# ADC.net
KiCad netlist of a schematic drawn in Altium Designer
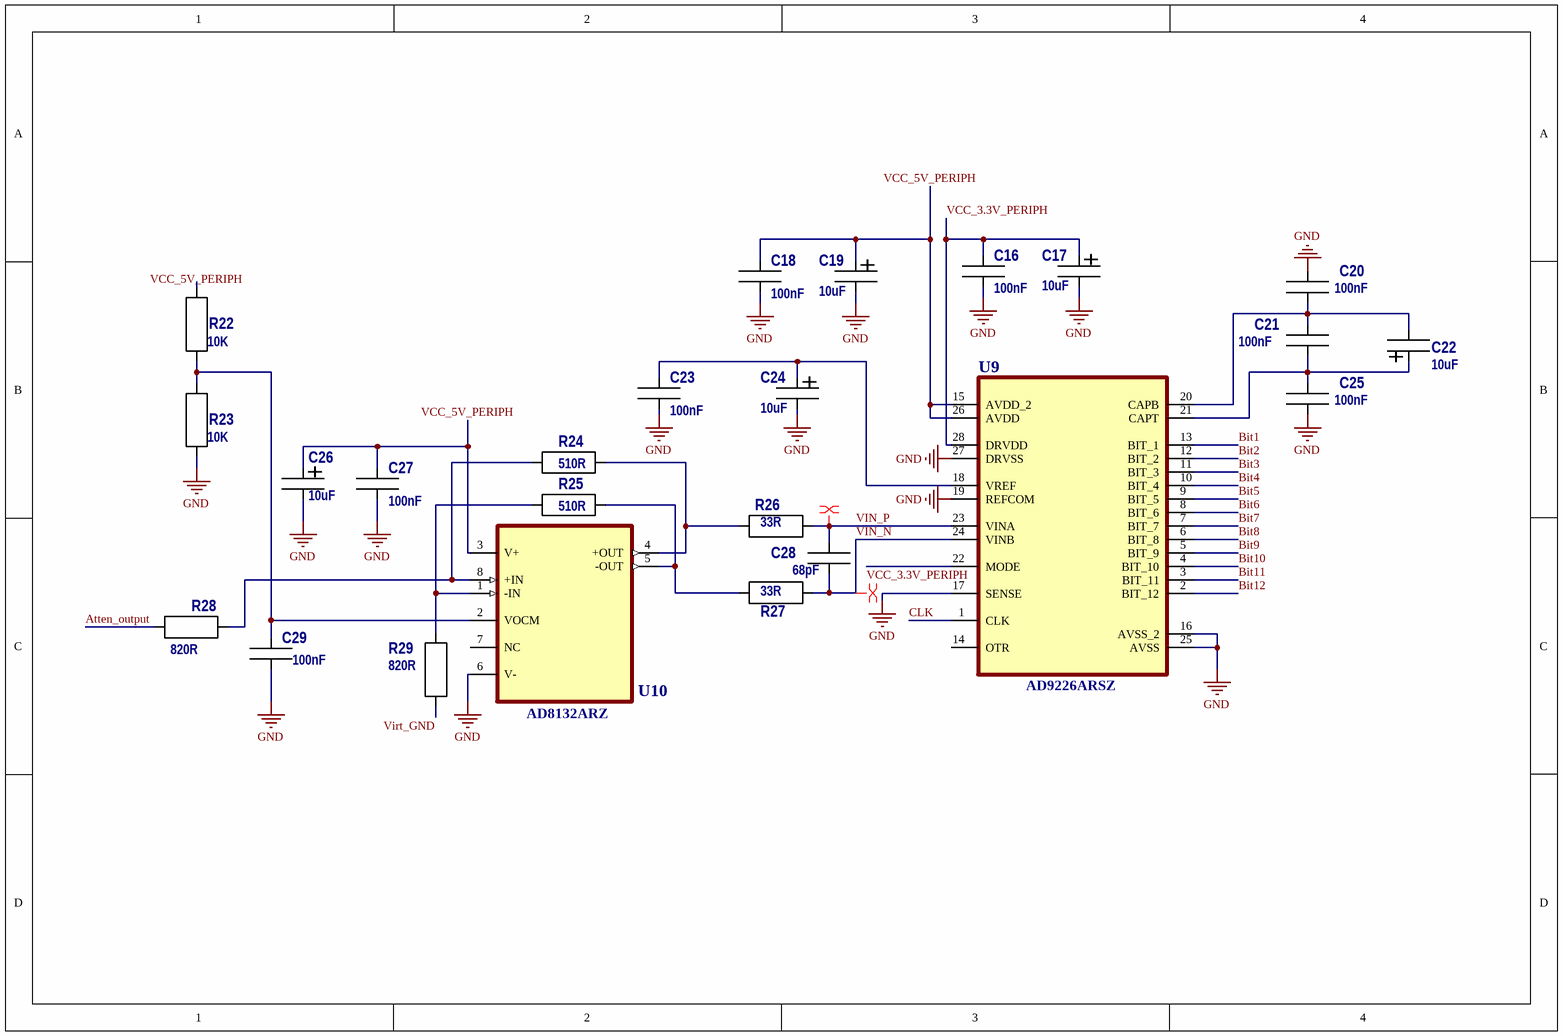
[diagram p0: ADC.SchDoc]

(export (version "E")
  (design (tool "Eeschema 10.0.6"))
  (components
    (comp (ref "C16")
      (value "100nF")
      (footprint "CAP 0603 3D")
      (description "0603 100nF X7R")
      (libsource (lib "RLC V7.1_BVI") (part "C"))
    )
    (comp (ref "C17")
      (value "10uF")
      (footprint "Tant B")
      (description "SMD type B 10 uF min 16V")
      (libsource (lib "RLC V7.1_BVI") (part "C T"))
    )
    (comp (ref "C18")
      (value "100nF")
      (footprint "CAP 0603 3D")
      (description "0603 100nF X7R")
      (libsource (lib "RLC V7.1_BVI") (part "C"))
    )
    (comp (ref "C19")
      (value "10uF")
      (footprint "Tant B")
      (description "SMD type B 10 uF min 16V")
      (libsource (lib "RLC V7.1_BVI") (part "C T"))
    )
    (comp (ref "C20")
      (value "100nF")
      (footprint "CAP 0603 3D")
      (description "0603 100nF X7R")
      (libsource (lib "RLC V7.1_BVI") (part "C"))
    )
    (comp (ref "C21")
      (value "100nF")
      (footprint "CAP 0603 3D")
      (description "0603 100nF X7R")
      (libsource (lib "RLC V7.1_BVI") (part "C"))
    )
    (comp (ref "C22")
      (value "10uF")
      (footprint "Tant B")
      (description "SMD type B 10 uF min 16V")
      (libsource (lib "RLC V7.1_BVI") (part "C T"))
    )
    (comp (ref "C23")
      (value "100nF")
      (footprint "CAP 0603 3D")
      (description "0603 100nF X7R")
      (libsource (lib "RLC V7.1_BVI") (part "C"))
    )
    (comp (ref "C24")
      (value "10uF")
      (footprint "Tant B")
      (description "SMD type B 10 uF min 16V")
      (libsource (lib "RLC V7.1_BVI") (part "C T"))
    )
    (comp (ref "C25")
      (value "100nF")
      (footprint "CAP 0603 3D")
      (description "0603 100nF X7R")
      (libsource (lib "RLC V7.1_BVI") (part "C"))
    )
    (comp (ref "C26")
      (value "10uF")
      (footprint "Tant B")
      (description "SMD type B 10 uF min 16V")
      (libsource (lib "RLC V7.1_BVI") (part "C T"))
    )
    (comp (ref "C27")
      (value "100nF")
      (footprint "cap 1206 3D")
      (description "0603 100nF X7R")
      (libsource (lib "RLC V7.1_BVI") (part "C"))
    )
    (comp (ref "C28")
      (value "68pF")
      (footprint "CAP 0603 3D")
      (description "0805 68pF NP0 (C0G)")
      (libsource (lib "RLC V7.1_BVI") (part "C"))
    )
    (comp (ref "C29")
      (value "100nF")
      (footprint "CAP 0603 3D")
      (description "0603 100nF X7R")
      (libsource (lib "RLC V7.1_BVI") (part "C"))
    )
    (comp (ref "R22")
      (value "10K")
      (footprint "Res_0603 3D")
      (description "10K 0805")
      (libsource (lib "RLC V7.1_BVI") (part "R"))
    )
    (comp (ref "R23")
      (value "10K")
      (footprint "Res_0603 3D")
      (description "10K 0805")
      (libsource (lib "RLC V7.1_BVI") (part "R"))
    )
    (comp (ref "R24")
      (value "510R")
      (footprint "Res_0603 3D")
      (description "0805 0.1%")
      (libsource (lib "RLC V7.1_BVI") (part "R"))
    )
    (comp (ref "R25")
      (value "510R")
      (footprint "Res_0603 3D")
      (description "0805 0.1%")
      (libsource (lib "RLC V7.1_BVI") (part "R"))
    )
    (comp (ref "R26")
      (value "33R")
      (footprint "Res_0603 3D")
      (description "0805 0.1%")
      (libsource (lib "RLC V7.1_BVI") (part "R"))
    )
    (comp (ref "R27")
      (value "33R")
      (footprint "Res_0603 3D")
      (description "0805 0.1%")
      (libsource (lib "RLC V7.1_BVI") (part "R"))
    )
    (comp (ref "R28")
      (value "820R")
      (footprint "Res_0603 3D")
      (description "0805 0.1%")
      (libsource (lib "RLC V7.1_BVI") (part "R"))
    )
    (comp (ref "R29")
      (value "820R")
      (footprint "Res_0603 3D")
      (description "0805 0.1%")
      (libsource (lib "RLC V7.1_BVI") (part "R"))
    )
    (comp (ref "U9")
      (value "AD9226ARSZ")
      (footprint "SOP65P780X200-28N")
      (description "12-Bit, 65 MSPS Analog-to-Digital Converter")
      (fields (field (name "MF") "Analog Devices"))
      (libsource (lib "AD9226ARSZ") (part "AD9226ARSZ"))
    )
    (comp (ref "U10")
      (value "AD8132ARZ")
      (footprint "SOIC127P600X175-8N")
      (description "Low Cost, High Speed Differential Amplifier")
      (fields (field (name "MF") "Analog Devices"))
      (libsource (lib "AD8132ARZ") (part "AD8132ARZ"))
    )
  )
  (nets
    (net (code "1") (name "/Atten_output") (class "Default") (node (ref "R28") (pin "2") (pintype "passive")))
    (net (code "2") (name "/Bit1") (class "Default")
      (node (ref "U9") (pin "13") (pinfunction "BIT_1_13") (pintype "passive"))
    )
    (net (code "3") (name "/Bit2") (class "Default")
      (node (ref "U9") (pin "12") (pinfunction "BIT_2_12") (pintype "passive"))
    )
    (net (code "4") (name "/Bit3") (class "Default")
      (node (ref "U9") (pin "11") (pinfunction "BIT_3_11") (pintype "passive"))
    )
    (net (code "5") (name "/Bit4") (class "Default")
      (node (ref "U9") (pin "10") (pinfunction "BIT_4_10") (pintype "passive"))
    )
    (net (code "6") (name "/Bit5") (class "Default")
      (node (ref "U9") (pin "9") (pinfunction "BIT_5_9") (pintype "passive"))
    )
    (net (code "7") (name "/Bit6") (class "Default")
      (node (ref "U9") (pin "8") (pinfunction "BIT_6_8") (pintype "passive"))
    )
    (net (code "8") (name "/Bit7") (class "Default")
      (node (ref "U9") (pin "7") (pinfunction "BIT_7_7") (pintype "passive"))
    )
    (net (code "9") (name "/Bit8") (class "Default")
      (node (ref "U9") (pin "6") (pinfunction "BIT_8_6") (pintype "passive"))
    )
    (net (code "10") (name "/Bit9") (class "Default")
      (node (ref "U9") (pin "5") (pinfunction "BIT_9_5") (pintype "passive"))
    )
    (net (code "11") (name "/Bit10") (class "Default")
      (node (ref "U9") (pin "4") (pinfunction "BIT_10_4") (pintype "passive"))
    )
    (net (code "12") (name "/Bit11") (class "Default")
      (node (ref "U9") (pin "3") (pinfunction "BIT_11_3") (pintype "passive"))
    )
    (net (code "13") (name "/Bit12") (class "Default")
      (node (ref "U9") (pin "2") (pinfunction "BIT_12_2") (pintype "passive"))
    )
    (net (code "14") (name "/CLK") (class "Default")
      (node (ref "U9") (pin "1") (pinfunction "CLK_1") (pintype "passive"))
    )
    (net (code "15") (name "/VCC_3.3V_PERIPH") (class "Default")
      (node (ref "C16") (pin "1") (pintype "passive"))
      (node (ref "C17") (pin "1") (pinfunction "+_1") (pintype "passive"))
      (node (ref "U9") (pin "22") (pinfunction "MODE_22") (pintype "passive"))
      (node (ref "U9") (pin "28") (pinfunction "DRVDD_28") (pintype "passive"))
    )
    (net (code "16") (name "/VCC_5V_PERIPH") (class "Default")
      (node (ref "C18") (pin "1") (pintype "passive"))
      (node (ref "C19") (pin "1") (pinfunction "+_1") (pintype "passive"))
      (node (ref "C26") (pin "1") (pinfunction "+_1") (pintype "passive"))
      (node (ref "C27") (pin "1") (pintype "passive"))
      (node (ref "R22") (pin "2") (pintype "passive"))
      (node (ref "U10") (pin "3") (pinfunction "V+_3") (pintype "power_in"))
      (node (ref "U9") (pin "15") (pinfunction "AVDD_2_15") (pintype "passive"))
      (node (ref "U9") (pin "26") (pinfunction "AVDD_26") (pintype "passive"))
    )
    (net (code "17") (name "/VIN_N") (class "Default")
      (node (ref "C28") (pin "2") (pintype "passive"))
      (node (ref "R27") (pin "1") (pintype "passive"))
      (node (ref "U9") (pin "24") (pinfunction "VINB_24") (pintype "passive"))
    )
    (net (code "18") (name "/VIN_P") (class "Default")
      (node (ref "C28") (pin "1") (pintype "passive"))
      (node (ref "R26") (pin "1") (pintype "passive"))
      (node (ref "U9") (pin "23") (pinfunction "VINA_23") (pintype "passive"))
    )
    (net (code "19") (name "/Virt_GND") (class "Default") (node (ref "R29") (pin "2") (pintype "passive")))
    (net (code "20") (name "GND") (class "Default")
      (node (ref "C16") (pin "2") (pintype "passive"))
      (node (ref "C17") (pin "2") (pinfunction "-_2") (pintype "passive"))
      (node (ref "C18") (pin "2") (pintype "passive"))
      (node (ref "C19") (pin "2") (pinfunction "-_2") (pintype "passive"))
      (node (ref "C20") (pin "1") (pintype "passive"))
      (node (ref "C23") (pin "2") (pintype "passive"))
      (node (ref "C24") (pin "2") (pinfunction "-_2") (pintype "passive"))
      (node (ref "C25") (pin "2") (pintype "passive"))
      (node (ref "C26") (pin "2") (pinfunction "-_2") (pintype "passive"))
      (node (ref "C27") (pin "2") (pintype "passive"))
      (node (ref "C29") (pin "2") (pintype "passive"))
      (node (ref "R23") (pin "1") (pintype "passive"))
      (node (ref "U10") (pin "6") (pinfunction "V-_6") (pintype "power_in"))
      (node (ref "U9") (pin "16") (pinfunction "AVSS_2_16") (pintype "passive"))
      (node (ref "U9") (pin "17") (pinfunction "SENSE_17") (pintype "passive"))
      (node (ref "U9") (pin "19") (pinfunction "REFCOM_19") (pintype "passive"))
      (node (ref "U9") (pin "25") (pinfunction "AVSS_25") (pintype "passive"))
      (node (ref "U9") (pin "27") (pinfunction "DRVSS_27") (pintype "passive"))
    )
    (net (code "21") (name "Net-(C22-+)") (class "Default")
      (node (ref "C21") (pin "2") (pintype "passive"))
      (node (ref "C22") (pin "1") (pinfunction "+_1") (pintype "passive"))
      (node (ref "C25") (pin "1") (pintype "passive"))
      (node (ref "U9") (pin "21") (pinfunction "CAPT_21") (pintype "passive"))
    )
    (net (code "22") (name "Net-(C22--)") (class "Default")
      (node (ref "C20") (pin "2") (pintype "passive"))
      (node (ref "C21") (pin "1") (pintype "passive"))
      (node (ref "C22") (pin "2") (pinfunction "-_2") (pintype "passive"))
      (node (ref "U9") (pin "20") (pinfunction "CAPB_20") (pintype "passive"))
    )
    (net (code "23") (name "Net-(C24-+)") (class "Default")
      (node (ref "C23") (pin "1") (pintype "passive"))
      (node (ref "C24") (pin "1") (pinfunction "+_1") (pintype "passive"))
      (node (ref "U9") (pin "18") (pinfunction "VREF_18") (pintype "passive"))
    )
    (net (code "24") (name "Net-(U10-+IN)") (class "Default")
      (node (ref "R24") (pin "2") (pintype "passive"))
      (node (ref "R28") (pin "1") (pintype "passive"))
      (node (ref "U10") (pin "8") (pinfunction "+IN_8") (pintype "input"))
    )
    (net (code "25") (name "Net-(U10-+OUT)") (class "Default")
      (node (ref "R24") (pin "1") (pintype "passive"))
      (node (ref "R26") (pin "2") (pintype "passive"))
      (node (ref "U10") (pin "4") (pinfunction "+OUT_4") (pintype "output"))
    )
    (net (code "26") (name "Net-(U10--IN)") (class "Default")
      (node (ref "R25") (pin "2") (pintype "passive"))
      (node (ref "R29") (pin "1") (pintype "passive"))
      (node (ref "U10") (pin "1") (pinfunction "-IN_1") (pintype "input"))
    )
    (net (code "27") (name "Net-(U10--OUT)") (class "Default")
      (node (ref "R25") (pin "1") (pintype "passive"))
      (node (ref "R27") (pin "2") (pintype "passive"))
      (node (ref "U10") (pin "5") (pinfunction "-OUT_5") (pintype "output"))
    )
    (net (code "28") (name "Net-(U10-VOCM)") (class "Default")
      (node (ref "C29") (pin "1") (pintype "passive"))
      (node (ref "R22") (pin "1") (pintype "passive"))
      (node (ref "R23") (pin "2") (pintype "passive"))
      (node (ref "U10") (pin "2") (pinfunction "VOCM_2") (pintype "passive"))
    )
    (net (code "29") (name "unconnected-(U9-OTR-Pad14)") (class "Default")
      (node (ref "U9") (pin "14") (pinfunction "OTR_14") (pintype "passive"))
    )
    (net (code "30") (name "unconnected-(U10-NC-Pad7)") (class "Default")
      (node (ref "U10") (pin "7") (pinfunction "NC_7") (pintype "passive"))
    )
  )
)
